# dalibor-display.net
KiCad netlist of a schematic drawn in Altium Designer
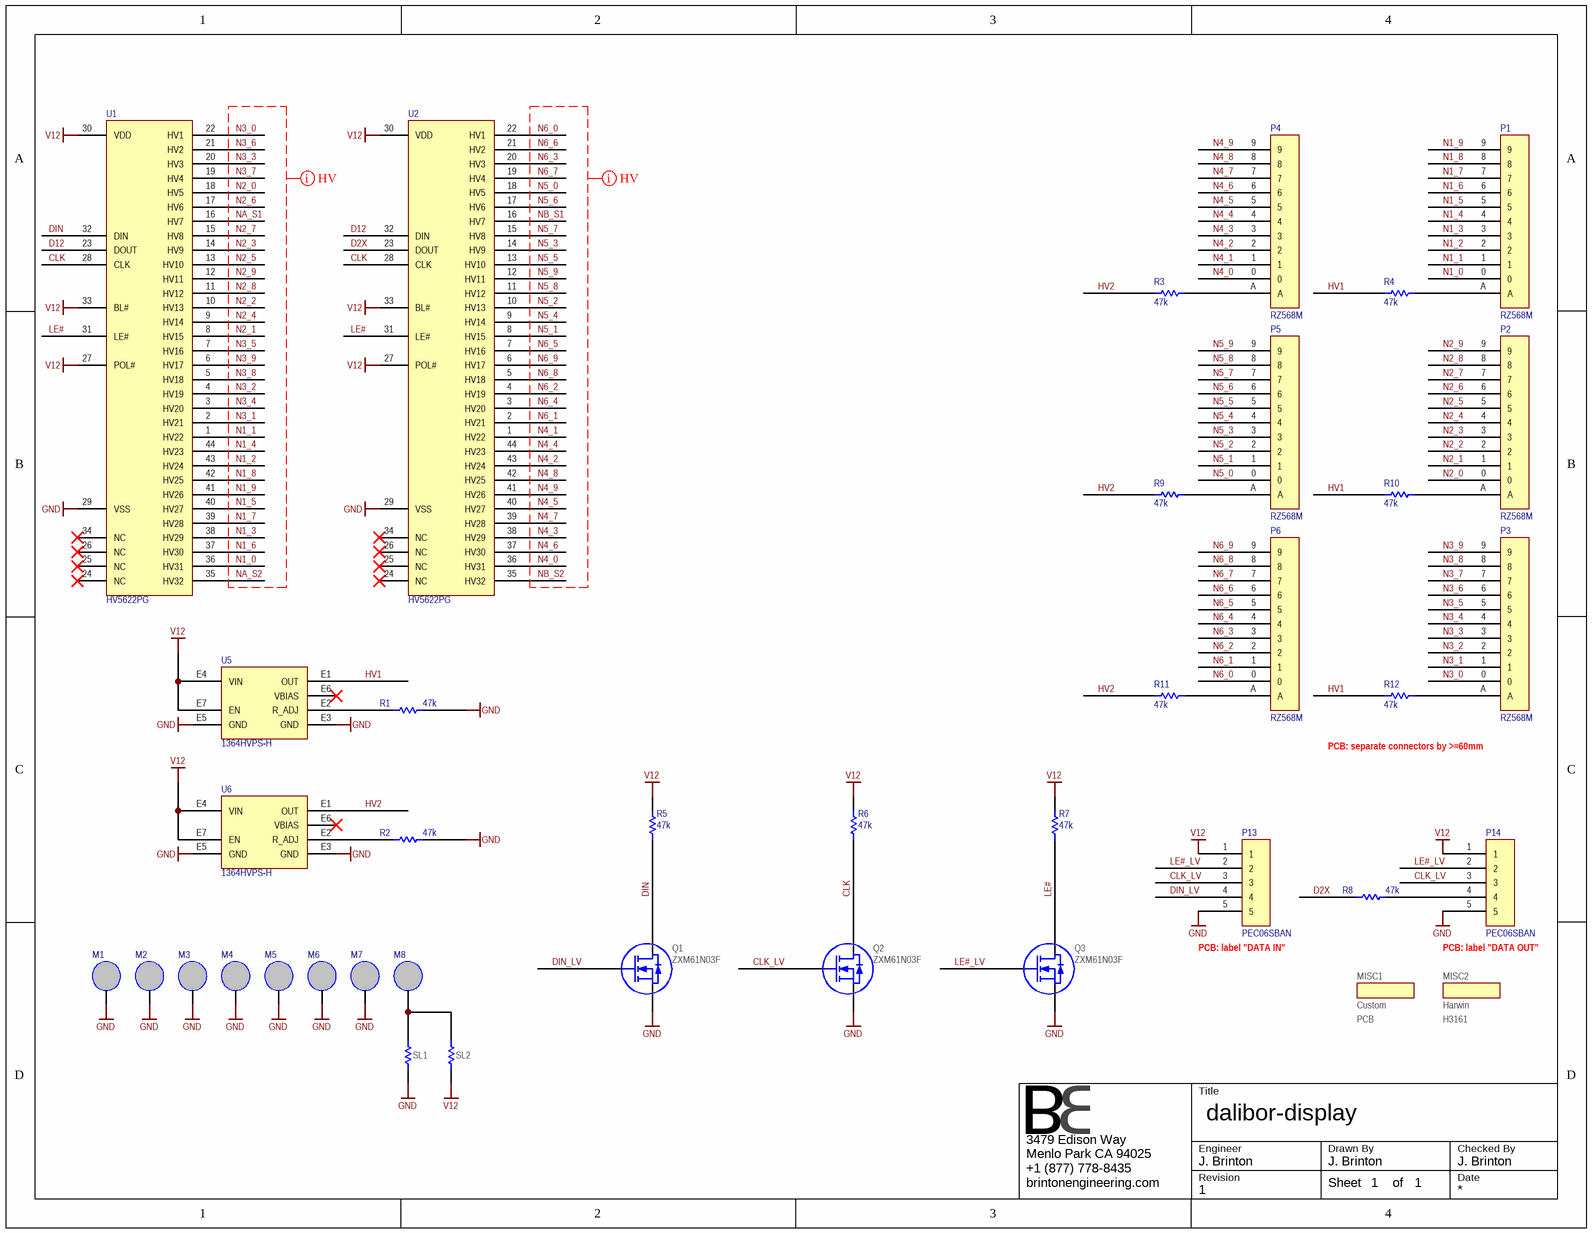
[diagram p0: dalibor-display.SchDoc]

(export (version "E")
  (design (tool "Eeschema 10.0.6"))
  (components
    (comp (ref "M1") (value "MOUNT") (footprint "MOUNT1-4_20") (libsource (lib "generic") (part "MOUNT")))
    (comp (ref "M2") (value "MOUNT") (footprint "MOUNT1-4_20") (libsource (lib "generic") (part "MOUNT")))
    (comp (ref "M3") (value "MOUNT") (footprint "MOUNT1-4_20") (libsource (lib "generic") (part "MOUNT")))
    (comp (ref "M4") (value "MOUNT") (footprint "MOUNT1-4_20") (libsource (lib "generic") (part "MOUNT")))
    (comp (ref "M5") (value "MOUNT") (footprint "MOUNT1-4_20") (libsource (lib "generic") (part "MOUNT")))
    (comp (ref "M6") (value "MOUNT") (footprint "MOUNT1-4_20") (libsource (lib "generic") (part "MOUNT")))
    (comp (ref "M7") (value "MOUNT") (footprint "MOUNT1-4_20") (libsource (lib "generic") (part "MOUNT")))
    (comp (ref "M8") (value "MOUNT") (footprint "MOUNT1-4_20") (libsource (lib "generic") (part "MOUNT")))
    (comp (ref "MISC1")
      (value "PCB")
      (fields (field (name "MANUFACTURER") "Custom"))
      (libsource (lib "harwin") (part "M50-1900005"))
    )
    (comp (ref "MISC2")
      (value "H3161")
      (description "Pin Receptacle")
      (fields (field (name "MANUFACTURER") "Harwin"))
      (libsource (lib "harwin") (part "M50-1900005"))
    )
    (comp (ref "P1")
      (value "RZ568M")
      (footprint "RZ568M")
      (description "Nixie Tube Socket")
      (fields (field (name "MANUFACTURER") "Glow Tube Research"))
      (libsource (lib "sigsub") (part "RZ568M"))
    )
    (comp (ref "P2")
      (value "RZ568M")
      (footprint "RZ568M")
      (description "Nixie Tube Socket")
      (fields (field (name "MANUFACTURER") "Glow Tube Research"))
      (libsource (lib "sigsub") (part "RZ568M"))
    )
    (comp (ref "P3")
      (value "RZ568M")
      (footprint "RZ568M")
      (description "Nixie Tube Socket")
      (fields (field (name "MANUFACTURER") "Glow Tube Research"))
      (libsource (lib "sigsub") (part "RZ568M"))
    )
    (comp (ref "P4")
      (value "RZ568M")
      (footprint "RZ568M")
      (description "Nixie Tube Socket")
      (fields (field (name "MANUFACTURER") "Glow Tube Research"))
      (libsource (lib "sigsub") (part "RZ568M"))
    )
    (comp (ref "P5")
      (value "RZ568M")
      (footprint "RZ568M")
      (description "Nixie Tube Socket")
      (fields (field (name "MANUFACTURER") "Glow Tube Research"))
      (libsource (lib "sigsub") (part "RZ568M"))
    )
    (comp (ref "P6")
      (value "RZ568M")
      (footprint "RZ568M")
      (description "Nixie Tube Socket")
      (fields (field (name "MANUFACTURER") "Glow Tube Research"))
      (libsource (lib "sigsub") (part "RZ568M"))
    )
    (comp (ref "P13")
      (value "PEC06SBAN")
      (footprint "HDR1X5")
      (description "Header, 5-Pin, Right Angle, 0.1\" pitch")
      (fields (field (name "MANUFACTURER") "Sullins"))
      (libsource (lib "sigsub") (part "PEC06SBAN"))
    )
    (comp (ref "P14")
      (value "PEC06SBAN")
      (footprint "HDR1X5")
      (description "Header, 5-Pin, Right Angle, 0.1\" pitch")
      (fields (field (name "MANUFACTURER") "Sullins"))
      (libsource (lib "sigsub") (part "PEC06SBAN"))
    )
    (comp (ref "Q1")
      (value "ZXM61N03F")
      (footprint "SOT23")
      (description "N-Channel Enhancement Mode MOSFET transistor")
      (fields (field (name "MANUFACTURER") "Zetex"))
      (libsource (lib "nxp") (part "BSH103"))
    )
    (comp (ref "Q2")
      (value "ZXM61N03F")
      (footprint "SOT23")
      (description "N-Channel Enhancement Mode MOSFET transistor")
      (fields (field (name "MANUFACTURER") "Zetex"))
      (libsource (lib "nxp") (part "BSH103"))
    )
    (comp (ref "Q3")
      (value "ZXM61N03F")
      (footprint "SOT23")
      (description "N-Channel Enhancement Mode MOSFET transistor")
      (fields (field (name "MANUFACTURER") "Zetex"))
      (libsource (lib "nxp") (part "BSH103"))
    )
    (comp (ref "R1")
      (value "47k")
      (footprint "0805")
      (description "Thick Film Resistor 47k +/-1% 0805")
      (fields (field (name "MANUFACTURER") "Panasonic") (field (name "Comment") "ERJ-6ENF4702V"))
      (libsource (lib "generic") (part "RES"))
    )
    (comp (ref "R2")
      (value "47k")
      (footprint "0805")
      (description "Thick Film Resistor 47k +/-1% 0805")
      (fields (field (name "MANUFACTURER") "Panasonic") (field (name "Comment") "ERJ-6ENF4702V"))
      (libsource (lib "generic") (part "RES"))
    )
    (comp (ref "R3")
      (value "47k")
      (footprint "0805")
      (description "Thick Film Resistor 47k +/-1% 0805")
      (fields (field (name "MANUFACTURER") "Panasonic") (field (name "Comment") "ERJ-6ENF4702V"))
      (libsource (lib "generic") (part "RES"))
    )
    (comp (ref "R4")
      (value "47k")
      (footprint "0805")
      (description "Thick Film Resistor 47k +/-1% 0805")
      (fields (field (name "MANUFACTURER") "Panasonic") (field (name "Comment") "ERJ-6ENF4702V"))
      (libsource (lib "generic") (part "RES"))
    )
    (comp (ref "R5")
      (value "47k")
      (footprint "0805")
      (description "Thick Film Resistor 47k +/-1% 0805")
      (fields (field (name "MANUFACTURER") "Panasonic") (field (name "Comment") "ERJ-6ENF4702V"))
      (libsource (lib "generic") (part "RES"))
    )
    (comp (ref "R6")
      (value "47k")
      (footprint "0805")
      (description "Thick Film Resistor 47k +/-1% 0805")
      (fields (field (name "MANUFACTURER") "Panasonic") (field (name "Comment") "ERJ-6ENF4702V"))
      (libsource (lib "generic") (part "RES"))
    )
    (comp (ref "R7")
      (value "47k")
      (footprint "0805")
      (description "Thick Film Resistor 47k +/-1% 0805")
      (fields (field (name "MANUFACTURER") "Panasonic") (field (name "Comment") "ERJ-6ENF4702V"))
      (libsource (lib "generic") (part "RES"))
    )
    (comp (ref "R8")
      (value "47k")
      (footprint "0805")
      (description "Thick Film Resistor 47k +/-1% 0805")
      (fields (field (name "MANUFACTURER") "Panasonic") (field (name "Comment") "ERJ-6ENF4702V"))
      (libsource (lib "generic") (part "RES"))
    )
    (comp (ref "R9")
      (value "47k")
      (footprint "0805")
      (description "Thick Film Resistor 47k +/-1% 0805")
      (fields (field (name "MANUFACTURER") "Panasonic") (field (name "Comment") "ERJ-6ENF4702V"))
      (libsource (lib "generic") (part "RES"))
    )
    (comp (ref "R10")
      (value "47k")
      (footprint "0805")
      (description "Thick Film Resistor 47k +/-1% 0805")
      (fields (field (name "MANUFACTURER") "Panasonic") (field (name "Comment") "ERJ-6ENF4702V"))
      (libsource (lib "generic") (part "RES"))
    )
    (comp (ref "R11")
      (value "47k")
      (footprint "0805")
      (description "Thick Film Resistor 47k +/-1% 0805")
      (fields (field (name "MANUFACTURER") "Panasonic") (field (name "Comment") "ERJ-6ENF4702V"))
      (libsource (lib "generic") (part "RES"))
    )
    (comp (ref "R12")
      (value "47k")
      (footprint "0805")
      (description "Thick Film Resistor 47k +/-1% 0805")
      (fields (field (name "MANUFACTURER") "Panasonic") (field (name "Comment") "ERJ-6ENF4702V"))
      (libsource (lib "generic") (part "RES"))
    )
    (comp (ref "SL1")
      (value "SOLDER_LINK")
      (footprint "SOLDERLINK0603X26N")
      (description "Solder Link")
      (libsource (lib "generic") (part "RES"))
    )
    (comp (ref "SL2")
      (value "SOLDER_LINK")
      (footprint "SOLDERLINK0603X26N")
      (description "Solder Link")
      (libsource (lib "generic") (part "RES"))
    )
    (comp (ref "U1")
      (value "HV5622PG")
      (footprint "QFP44P80_1390X1390X235L88X37N")
      (description "32-Channel Serial to Parallel Converter")
      (fields (field (name "MANUFACTURER") "Microchip"))
      (libsource (lib "sigsub") (part "HV5622PG"))
    )
    (comp (ref "U2")
      (value "HV5622PG")
      (footprint "QFP44P80_1390X1390X235L88X37N")
      (description "32-Channel Serial to Parallel Converter")
      (fields (field (name "MANUFACTURER") "Microchip"))
      (libsource (lib "sigsub") (part "HV5622PG"))
    )
    (comp (ref "U5")
      (value "1364HVPS-H")
      (footprint "1364HVPS-H")
      (description "High Voltage Power Supply")
      (fields (field (name "MANUFACTURER") "Taylor Electronics"))
      (libsource (lib "sigsub") (part "1364HVPS-H"))
    )
    (comp (ref "U6")
      (value "1364HVPS-H")
      (footprint "1364HVPS-H")
      (description "High Voltage Power Supply")
      (fields (field (name "MANUFACTURER") "Taylor Electronics"))
      (libsource (lib "sigsub") (part "1364HVPS-H"))
    )
  )
  (nets
    (net (code "1") (name "/CLK") (class "Default")
      (node (ref "Q2") (pin "3") (pinfunction "D_3") (pintype "passive"))
      (node (ref "R6") (pin "1") (pinfunction "1_1") (pintype "passive"))
      (node (ref "U1") (pin "28") (pinfunction "CLK_28") (pintype "passive"))
      (node (ref "U2") (pin "28") (pinfunction "CLK_28") (pintype "passive"))
    )
    (net (code "2") (name "/CLK_LV") (class "Default")
      (node (ref "P13") (pin "3") (pinfunction "3_3") (pintype "passive"))
      (node (ref "P14") (pin "3") (pinfunction "3_3") (pintype "passive"))
      (node (ref "Q2") (pin "1") (pinfunction "G_1") (pintype "passive"))
    )
    (net (code "3") (name "/D2X") (class "Default")
      (node (ref "R8") (pin "1") (pinfunction "1_1") (pintype "passive"))
      (node (ref "U2") (pin "23") (pinfunction "DOUT_23") (pintype "passive"))
    )
    (net (code "4") (name "/D12") (class "Default")
      (node (ref "U1") (pin "23") (pinfunction "DOUT_23") (pintype "passive"))
      (node (ref "U2") (pin "32") (pinfunction "DIN_32") (pintype "passive"))
    )
    (net (code "5") (name "/DIN") (class "Default")
      (node (ref "Q1") (pin "3") (pinfunction "D_3") (pintype "passive"))
      (node (ref "R5") (pin "1") (pinfunction "1_1") (pintype "passive"))
      (node (ref "U1") (pin "32") (pinfunction "DIN_32") (pintype "passive"))
    )
    (net (code "6") (name "/DIN_LV") (class "Default")
      (node (ref "P13") (pin "4") (pinfunction "4_4") (pintype "passive"))
      (node (ref "Q1") (pin "1") (pinfunction "G_1") (pintype "passive"))
    )
    (net (code "7") (name "/HV1") (class "Default")
      (node (ref "R10") (pin "2") (pinfunction "2_2") (pintype "passive"))
      (node (ref "R12") (pin "2") (pinfunction "2_2") (pintype "passive"))
      (node (ref "R4") (pin "2") (pinfunction "2_2") (pintype "passive"))
      (node (ref "U5") (pin "E1") (pinfunction "OUT_E1") (pintype "passive"))
    )
    (net (code "8") (name "/HV2") (class "Default")
      (node (ref "R11") (pin "2") (pinfunction "2_2") (pintype "passive"))
      (node (ref "R3") (pin "2") (pinfunction "2_2") (pintype "passive"))
      (node (ref "R9") (pin "2") (pinfunction "2_2") (pintype "passive"))
      (node (ref "U6") (pin "E1") (pinfunction "OUT_E1") (pintype "passive"))
    )
    (net (code "9") (name "/LE#") (class "Default")
      (node (ref "Q3") (pin "3") (pinfunction "D_3") (pintype "passive"))
      (node (ref "R7") (pin "1") (pinfunction "1_1") (pintype "passive"))
      (node (ref "U1") (pin "31") (pinfunction "LE#_31") (pintype "passive"))
      (node (ref "U2") (pin "31") (pinfunction "LE#_31") (pintype "passive"))
    )
    (net (code "10") (name "/LE#_LV") (class "Default")
      (node (ref "P13") (pin "2") (pinfunction "2_2") (pintype "passive"))
      (node (ref "P14") (pin "2") (pinfunction "2_2") (pintype "passive"))
      (node (ref "Q3") (pin "1") (pinfunction "G_1") (pintype "passive"))
    )
    (net (code "11") (name "/N1_0") (class "Default")
      (node (ref "P1") (pin "0") (pinfunction "0_0") (pintype "passive"))
      (node (ref "U1") (pin "36") (pinfunction "HV31_36") (pintype "passive"))
    )
    (net (code "12") (name "/N1_1") (class "Default")
      (node (ref "P1") (pin "1") (pinfunction "1_1") (pintype "passive"))
      (node (ref "U1") (pin "1") (pinfunction "HV22_1") (pintype "passive"))
    )
    (net (code "13") (name "/N1_2") (class "Default")
      (node (ref "P1") (pin "2") (pinfunction "2_2") (pintype "passive"))
      (node (ref "U1") (pin "43") (pinfunction "HV24_43") (pintype "passive"))
    )
    (net (code "14") (name "/N1_3") (class "Default")
      (node (ref "P1") (pin "3") (pinfunction "3_3") (pintype "passive"))
      (node (ref "U1") (pin "38") (pinfunction "HV29_38") (pintype "passive"))
    )
    (net (code "15") (name "/N1_4") (class "Default")
      (node (ref "P1") (pin "4") (pinfunction "4_4") (pintype "passive"))
      (node (ref "U1") (pin "44") (pinfunction "HV23_44") (pintype "passive"))
    )
    (net (code "16") (name "/N1_5") (class "Default")
      (node (ref "P1") (pin "5") (pinfunction "5_5") (pintype "passive"))
      (node (ref "U1") (pin "40") (pinfunction "HV27_40") (pintype "passive"))
    )
    (net (code "17") (name "/N1_6") (class "Default")
      (node (ref "P1") (pin "6") (pinfunction "6_6") (pintype "passive"))
      (node (ref "U1") (pin "37") (pinfunction "HV30_37") (pintype "passive"))
    )
    (net (code "18") (name "/N1_7") (class "Default")
      (node (ref "P1") (pin "7") (pinfunction "7_7") (pintype "passive"))
      (node (ref "U1") (pin "39") (pinfunction "HV28_39") (pintype "passive"))
    )
    (net (code "19") (name "/N1_8") (class "Default")
      (node (ref "P1") (pin "8") (pinfunction "8_8") (pintype "passive"))
      (node (ref "U1") (pin "42") (pinfunction "HV25_42") (pintype "passive"))
    )
    (net (code "20") (name "/N1_9") (class "Default")
      (node (ref "P1") (pin "9") (pinfunction "9_9") (pintype "passive"))
      (node (ref "U1") (pin "41") (pinfunction "HV26_41") (pintype "passive"))
    )
    (net (code "21") (name "/N2_0") (class "Default")
      (node (ref "P2") (pin "0") (pinfunction "0_0") (pintype "passive"))
      (node (ref "U1") (pin "18") (pinfunction "HV5_18") (pintype "passive"))
    )
    (net (code "22") (name "/N2_1") (class "Default")
      (node (ref "P2") (pin "1") (pinfunction "1_1") (pintype "passive"))
      (node (ref "U1") (pin "8") (pinfunction "HV15_8") (pintype "passive"))
    )
    (net (code "23") (name "/N2_2") (class "Default")
      (node (ref "P2") (pin "2") (pinfunction "2_2") (pintype "passive"))
      (node (ref "U1") (pin "10") (pinfunction "HV13_10") (pintype "passive"))
    )
    (net (code "24") (name "/N2_3") (class "Default")
      (node (ref "P2") (pin "3") (pinfunction "3_3") (pintype "passive"))
      (node (ref "U1") (pin "14") (pinfunction "HV9_14") (pintype "passive"))
    )
    (net (code "25") (name "/N2_4") (class "Default")
      (node (ref "P2") (pin "4") (pinfunction "4_4") (pintype "passive"))
      (node (ref "U1") (pin "9") (pinfunction "HV14_9") (pintype "passive"))
    )
    (net (code "26") (name "/N2_5") (class "Default")
      (node (ref "P2") (pin "5") (pinfunction "5_5") (pintype "passive"))
      (node (ref "U1") (pin "13") (pinfunction "HV10_13") (pintype "passive"))
    )
    (net (code "27") (name "/N2_6") (class "Default")
      (node (ref "P2") (pin "6") (pinfunction "6_6") (pintype "passive"))
      (node (ref "U1") (pin "17") (pinfunction "HV6_17") (pintype "passive"))
    )
    (net (code "28") (name "/N2_7") (class "Default")
      (node (ref "P2") (pin "7") (pinfunction "7_7") (pintype "passive"))
      (node (ref "U1") (pin "15") (pinfunction "HV8_15") (pintype "passive"))
    )
    (net (code "29") (name "/N2_8") (class "Default")
      (node (ref "P2") (pin "8") (pinfunction "8_8") (pintype "passive"))
      (node (ref "U1") (pin "11") (pinfunction "HV12_11") (pintype "passive"))
    )
    (net (code "30") (name "/N2_9") (class "Default")
      (node (ref "P2") (pin "9") (pinfunction "9_9") (pintype "passive"))
      (node (ref "U1") (pin "12") (pinfunction "HV11_12") (pintype "passive"))
    )
    (net (code "31") (name "/N3_0") (class "Default")
      (node (ref "P3") (pin "0") (pinfunction "0_0") (pintype "passive"))
      (node (ref "U1") (pin "22") (pinfunction "HV1_22") (pintype "passive"))
    )
    (net (code "32") (name "/N3_1") (class "Default")
      (node (ref "P3") (pin "1") (pinfunction "1_1") (pintype "passive"))
      (node (ref "U1") (pin "2") (pinfunction "HV21_2") (pintype "passive"))
    )
    (net (code "33") (name "/N3_2") (class "Default")
      (node (ref "P3") (pin "2") (pinfunction "2_2") (pintype "passive"))
      (node (ref "U1") (pin "4") (pinfunction "HV19_4") (pintype "passive"))
    )
    (net (code "34") (name "/N3_3") (class "Default")
      (node (ref "P3") (pin "3") (pinfunction "3_3") (pintype "passive"))
      (node (ref "U1") (pin "20") (pinfunction "HV3_20") (pintype "passive"))
    )
    (net (code "35") (name "/N3_4") (class "Default")
      (node (ref "P3") (pin "4") (pinfunction "4_4") (pintype "passive"))
      (node (ref "U1") (pin "3") (pinfunction "HV20_3") (pintype "passive"))
    )
    (net (code "36") (name "/N3_5") (class "Default")
      (node (ref "P3") (pin "5") (pinfunction "5_5") (pintype "passive"))
      (node (ref "U1") (pin "7") (pinfunction "HV16_7") (pintype "passive"))
    )
    (net (code "37") (name "/N3_6") (class "Default")
      (node (ref "P3") (pin "6") (pinfunction "6_6") (pintype "passive"))
      (node (ref "U1") (pin "21") (pinfunction "HV2_21") (pintype "passive"))
    )
    (net (code "38") (name "/N3_7") (class "Default")
      (node (ref "P3") (pin "7") (pinfunction "7_7") (pintype "passive"))
      (node (ref "U1") (pin "19") (pinfunction "HV4_19") (pintype "passive"))
    )
    (net (code "39") (name "/N3_8") (class "Default")
      (node (ref "P3") (pin "8") (pinfunction "8_8") (pintype "passive"))
      (node (ref "U1") (pin "5") (pinfunction "HV18_5") (pintype "passive"))
    )
    (net (code "40") (name "/N3_9") (class "Default")
      (node (ref "P3") (pin "9") (pinfunction "9_9") (pintype "passive"))
      (node (ref "U1") (pin "6") (pinfunction "HV17_6") (pintype "passive"))
    )
    (net (code "41") (name "/N4_0") (class "Default")
      (node (ref "P4") (pin "0") (pinfunction "0_0") (pintype "passive"))
      (node (ref "U2") (pin "36") (pinfunction "HV31_36") (pintype "passive"))
    )
    (net (code "42") (name "/N4_1") (class "Default")
      (node (ref "P4") (pin "1") (pinfunction "1_1") (pintype "passive"))
      (node (ref "U2") (pin "1") (pinfunction "HV22_1") (pintype "passive"))
    )
    (net (code "43") (name "/N4_2") (class "Default")
      (node (ref "P4") (pin "2") (pinfunction "2_2") (pintype "passive"))
      (node (ref "U2") (pin "43") (pinfunction "HV24_43") (pintype "passive"))
    )
    (net (code "44") (name "/N4_3") (class "Default")
      (node (ref "P4") (pin "3") (pinfunction "3_3") (pintype "passive"))
      (node (ref "U2") (pin "38") (pinfunction "HV29_38") (pintype "passive"))
    )
    (net (code "45") (name "/N4_4") (class "Default")
      (node (ref "P4") (pin "4") (pinfunction "4_4") (pintype "passive"))
      (node (ref "U2") (pin "44") (pinfunction "HV23_44") (pintype "passive"))
    )
    (net (code "46") (name "/N4_5") (class "Default")
      (node (ref "P4") (pin "5") (pinfunction "5_5") (pintype "passive"))
      (node (ref "U2") (pin "40") (pinfunction "HV27_40") (pintype "passive"))
    )
    (net (code "47") (name "/N4_6") (class "Default")
      (node (ref "P4") (pin "6") (pinfunction "6_6") (pintype "passive"))
      (node (ref "U2") (pin "37") (pinfunction "HV30_37") (pintype "passive"))
    )
    (net (code "48") (name "/N4_7") (class "Default")
      (node (ref "P4") (pin "7") (pinfunction "7_7") (pintype "passive"))
      (node (ref "U2") (pin "39") (pinfunction "HV28_39") (pintype "passive"))
    )
    (net (code "49") (name "/N4_8") (class "Default")
      (node (ref "P4") (pin "8") (pinfunction "8_8") (pintype "passive"))
      (node (ref "U2") (pin "42") (pinfunction "HV25_42") (pintype "passive"))
    )
    (net (code "50") (name "/N4_9") (class "Default")
      (node (ref "P4") (pin "9") (pinfunction "9_9") (pintype "passive"))
      (node (ref "U2") (pin "41") (pinfunction "HV26_41") (pintype "passive"))
    )
    (net (code "51") (name "/N5_0") (class "Default")
      (node (ref "P5") (pin "0") (pinfunction "0_0") (pintype "passive"))
      (node (ref "U2") (pin "18") (pinfunction "HV5_18") (pintype "passive"))
    )
    (net (code "52") (name "/N5_1") (class "Default")
      (node (ref "P5") (pin "1") (pinfunction "1_1") (pintype "passive"))
      (node (ref "U2") (pin "8") (pinfunction "HV15_8") (pintype "passive"))
    )
    (net (code "53") (name "/N5_2") (class "Default")
      (node (ref "P5") (pin "2") (pinfunction "2_2") (pintype "passive"))
      (node (ref "U2") (pin "10") (pinfunction "HV13_10") (pintype "passive"))
    )
    (net (code "54") (name "/N5_3") (class "Default")
      (node (ref "P5") (pin "3") (pinfunction "3_3") (pintype "passive"))
      (node (ref "U2") (pin "14") (pinfunction "HV9_14") (pintype "passive"))
    )
    (net (code "55") (name "/N5_4") (class "Default")
      (node (ref "P5") (pin "4") (pinfunction "4_4") (pintype "passive"))
      (node (ref "U2") (pin "9") (pinfunction "HV14_9") (pintype "passive"))
    )
    (net (code "56") (name "/N5_5") (class "Default")
      (node (ref "P5") (pin "5") (pinfunction "5_5") (pintype "passive"))
      (node (ref "U2") (pin "13") (pinfunction "HV10_13") (pintype "passive"))
    )
    (net (code "57") (name "/N5_6") (class "Default")
      (node (ref "P5") (pin "6") (pinfunction "6_6") (pintype "passive"))
      (node (ref "U2") (pin "17") (pinfunction "HV6_17") (pintype "passive"))
    )
    (net (code "58") (name "/N5_7") (class "Default")
      (node (ref "P5") (pin "7") (pinfunction "7_7") (pintype "passive"))
      (node (ref "U2") (pin "15") (pinfunction "HV8_15") (pintype "passive"))
    )
    (net (code "59") (name "/N5_8") (class "Default")
      (node (ref "P5") (pin "8") (pinfunction "8_8") (pintype "passive"))
      (node (ref "U2") (pin "11") (pinfunction "HV12_11") (pintype "passive"))
    )
    (net (code "60") (name "/N5_9") (class "Default")
      (node (ref "P5") (pin "9") (pinfunction "9_9") (pintype "passive"))
      (node (ref "U2") (pin "12") (pinfunction "HV11_12") (pintype "passive"))
    )
    (net (code "61") (name "/N6_0") (class "Default")
      (node (ref "P6") (pin "0") (pinfunction "0_0") (pintype "passive"))
      (node (ref "U2") (pin "22") (pinfunction "HV1_22") (pintype "passive"))
    )
    (net (code "62") (name "/N6_1") (class "Default")
      (node (ref "P6") (pin "1") (pinfunction "1_1") (pintype "passive"))
      (node (ref "U2") (pin "2") (pinfunction "HV21_2") (pintype "passive"))
    )
    (net (code "63") (name "/N6_2") (class "Default")
      (node (ref "P6") (pin "2") (pinfunction "2_2") (pintype "passive"))
      (node (ref "U2") (pin "4") (pinfunction "HV19_4") (pintype "passive"))
    )
    (net (code "64") (name "/N6_3") (class "Default")
      (node (ref "P6") (pin "3") (pinfunction "3_3") (pintype "passive"))
      (node (ref "U2") (pin "20") (pinfunction "HV3_20") (pintype "passive"))
    )
    (net (code "65") (name "/N6_4") (class "Default")
      (node (ref "P6") (pin "4") (pinfunction "4_4") (pintype "passive"))
      (node (ref "U2") (pin "3") (pinfunction "HV20_3") (pintype "passive"))
    )
    (net (code "66") (name "/N6_5") (class "Default")
      (node (ref "P6") (pin "5") (pinfunction "5_5") (pintype "passive"))
      (node (ref "U2") (pin "7") (pinfunction "HV16_7") (pintype "passive"))
    )
    (net (code "67") (name "/N6_6") (class "Default")
      (node (ref "P6") (pin "6") (pinfunction "6_6") (pintype "passive"))
      (node (ref "U2") (pin "21") (pinfunction "HV2_21") (pintype "passive"))
    )
    (net (code "68") (name "/N6_7") (class "Default")
      (node (ref "P6") (pin "7") (pinfunction "7_7") (pintype "passive"))
      (node (ref "U2") (pin "19") (pinfunction "HV4_19") (pintype "passive"))
    )
    (net (code "69") (name "/N6_8") (class "Default")
      (node (ref "P6") (pin "8") (pinfunction "8_8") (pintype "passive"))
      (node (ref "U2") (pin "5") (pinfunction "HV18_5") (pintype "passive"))
    )
    (net (code "70") (name "/N6_9") (class "Default")
      (node (ref "P6") (pin "9") (pinfunction "9_9") (pintype "passive"))
      (node (ref "U2") (pin "6") (pinfunction "HV17_6") (pintype "passive"))
    )
    (net (code "71") (name "/NA_S1") (class "Default")
      (node (ref "U1") (pin "16") (pinfunction "HV7_16") (pintype "passive"))
    )
    (net (code "72") (name "/NA_S2") (class "Default")
      (node (ref "U1") (pin "35") (pinfunction "HV32_35") (pintype "passive"))
    )
    (net (code "73") (name "/NB_S1") (class "Default")
      (node (ref "U2") (pin "16") (pinfunction "HV7_16") (pintype "passive"))
    )
    (net (code "74") (name "/NB_S2") (class "Default")
      (node (ref "U2") (pin "35") (pinfunction "HV32_35") (pintype "passive"))
    )
    (net (code "75") (name "GND") (class "Default")
      (node (ref "M1") (pin "1") (pinfunction "MNT_1") (pintype "passive"))
      (node (ref "M2") (pin "1") (pinfunction "MNT_1") (pintype "passive"))
      (node (ref "M3") (pin "1") (pinfunction "MNT_1") (pintype "passive"))
      (node (ref "M4") (pin "1") (pinfunction "MNT_1") (pintype "passive"))
      (node (ref "M5") (pin "1") (pinfunction "MNT_1") (pintype "passive"))
      (node (ref "M6") (pin "1") (pinfunction "MNT_1") (pintype "passive"))
      (node (ref "M7") (pin "1") (pinfunction "MNT_1") (pintype "passive"))
      (node (ref "P13") (pin "5") (pinfunction "5_5") (pintype "passive"))
      (node (ref "P14") (pin "5") (pinfunction "5_5") (pintype "passive"))
      (node (ref "Q1") (pin "2") (pinfunction "S_2") (pintype "passive"))
      (node (ref "Q2") (pin "2") (pinfunction "S_2") (pintype "passive"))
      (node (ref "Q3") (pin "2") (pinfunction "S_2") (pintype "passive"))
      (node (ref "R1") (pin "2") (pinfunction "2_2") (pintype "passive"))
      (node (ref "R2") (pin "2") (pinfunction "2_2") (pintype "passive"))
      (node (ref "SL1") (pin "2") (pinfunction "2_2") (pintype "passive"))
      (node (ref "U1") (pin "29") (pinfunction "VSS_29") (pintype "passive"))
      (node (ref "U2") (pin "29") (pinfunction "VSS_29") (pintype "passive"))
      (node (ref "U5") (pin "E3") (pinfunction "GND_E3") (pintype "passive"))
      (node (ref "U5") (pin "E5") (pinfunction "GND_E5") (pintype "passive"))
      (node (ref "U6") (pin "E3") (pinfunction "GND_E3") (pintype "passive"))
      (node (ref "U6") (pin "E5") (pinfunction "GND_E5") (pintype "passive"))
    )
    (net (code "76") (name "Net-(M8-MNT)") (class "Default")
      (node (ref "M8") (pin "1") (pinfunction "MNT_1") (pintype "passive"))
      (node (ref "SL1") (pin "1") (pinfunction "1_1") (pintype "passive"))
      (node (ref "SL2") (pin "1") (pinfunction "1_1") (pintype "passive"))
    )
    (net (code "77") (name "Net-(P1-PadA)") (class "Default")
      (node (ref "P1") (pin "A") (pinfunction "A_A") (pintype "passive"))
      (node (ref "R4") (pin "1") (pinfunction "1_1") (pintype "passive"))
    )
    (net (code "78") (name "Net-(P2-PadA)") (class "Default")
      (node (ref "P2") (pin "A") (pinfunction "A_A") (pintype "passive"))
      (node (ref "R10") (pin "1") (pinfunction "1_1") (pintype "passive"))
    )
    (net (code "79") (name "Net-(P3-PadA)") (class "Default")
      (node (ref "P3") (pin "A") (pinfunction "A_A") (pintype "passive"))
      (node (ref "R12") (pin "1") (pinfunction "1_1") (pintype "passive"))
    )
    (net (code "80") (name "Net-(P4-PadA)") (class "Default")
      (node (ref "P4") (pin "A") (pinfunction "A_A") (pintype "passive"))
      (node (ref "R3") (pin "1") (pinfunction "1_1") (pintype "passive"))
    )
    (net (code "81") (name "Net-(P5-PadA)") (class "Default")
      (node (ref "P5") (pin "A") (pinfunction "A_A") (pintype "passive"))
      (node (ref "R9") (pin "1") (pinfunction "1_1") (pintype "passive"))
    )
    (net (code "82") (name "Net-(P6-PadA)") (class "Default")
      (node (ref "P6") (pin "A") (pinfunction "A_A") (pintype "passive"))
      (node (ref "R11") (pin "1") (pinfunction "1_1") (pintype "passive"))
    )
    (net (code "83") (name "Net-(P14-Pad4)") (class "Default")
      (node (ref "P14") (pin "4") (pinfunction "4_4") (pintype "passive"))
      (node (ref "R8") (pin "2") (pinfunction "2_2") (pintype "passive"))
    )
    (net (code "84") (name "Net-(U5-R_ADJ)") (class "Default")
      (node (ref "R1") (pin "1") (pinfunction "1_1") (pintype "passive"))
      (node (ref "U5") (pin "E2") (pinfunction "R_ADJ_E2") (pintype "passive"))
    )
    (net (code "85") (name "Net-(U6-R_ADJ)") (class "Default")
      (node (ref "R2") (pin "1") (pinfunction "1_1") (pintype "passive"))
      (node (ref "U6") (pin "E2") (pinfunction "R_ADJ_E2") (pintype "passive"))
    )
    (net (code "86") (name "V12") (class "Default")
      (node (ref "P13") (pin "1") (pinfunction "1_1") (pintype "passive"))
      (node (ref "P14") (pin "1") (pinfunction "1_1") (pintype "passive"))
      (node (ref "R5") (pin "2") (pinfunction "2_2") (pintype "passive"))
      (node (ref "R6") (pin "2") (pinfunction "2_2") (pintype "passive"))
      (node (ref "R7") (pin "2") (pinfunction "2_2") (pintype "passive"))
      (node (ref "SL2") (pin "2") (pinfunction "2_2") (pintype "passive"))
      (node (ref "U1") (pin "27") (pinfunction "POL#_27") (pintype "passive"))
      (node (ref "U1") (pin "30") (pinfunction "VDD_30") (pintype "passive"))
      (node (ref "U1") (pin "33") (pinfunction "BL#_33") (pintype "passive"))
      (node (ref "U2") (pin "27") (pinfunction "POL#_27") (pintype "passive"))
      (node (ref "U2") (pin "30") (pinfunction "VDD_30") (pintype "passive"))
      (node (ref "U2") (pin "33") (pinfunction "BL#_33") (pintype "passive"))
      (node (ref "U5") (pin "E4") (pinfunction "VIN_E4") (pintype "passive"))
      (node (ref "U5") (pin "E7") (pinfunction "EN_E7") (pintype "passive"))
      (node (ref "U6") (pin "E4") (pinfunction "VIN_E4") (pintype "passive"))
      (node (ref "U6") (pin "E7") (pinfunction "EN_E7") (pintype "passive"))
    )
    (net (code "87") (name "unconnected-(U1-NC-Pad24)") (class "Default")
      (node (ref "U1") (pin "24") (pinfunction "NC_24") (pintype "passive+no_connect"))
    )
    (net (code "88") (name "unconnected-(U1-NC-Pad25)") (class "Default")
      (node (ref "U1") (pin "25") (pinfunction "NC_25") (pintype "passive+no_connect"))
    )
    (net (code "89") (name "unconnected-(U1-NC-Pad26)") (class "Default")
      (node (ref "U1") (pin "26") (pinfunction "NC_26") (pintype "passive+no_connect"))
    )
    (net (code "90") (name "unconnected-(U1-NC-Pad34)") (class "Default")
      (node (ref "U1") (pin "34") (pinfunction "NC_34") (pintype "passive+no_connect"))
    )
    (net (code "91") (name "unconnected-(U2-NC-Pad24)") (class "Default")
      (node (ref "U2") (pin "24") (pinfunction "NC_24") (pintype "passive+no_connect"))
    )
    (net (code "92") (name "unconnected-(U2-NC-Pad25)") (class "Default")
      (node (ref "U2") (pin "25") (pinfunction "NC_25") (pintype "passive+no_connect"))
    )
    (net (code "93") (name "unconnected-(U2-NC-Pad26)") (class "Default")
      (node (ref "U2") (pin "26") (pinfunction "NC_26") (pintype "passive+no_connect"))
    )
    (net (code "94") (name "unconnected-(U2-NC-Pad34)") (class "Default")
      (node (ref "U2") (pin "34") (pinfunction "NC_34") (pintype "passive+no_connect"))
    )
    (net (code "95") (name "unconnected-(U5-VBIAS-PadE6)") (class "Default")
      (node (ref "U5") (pin "E6") (pinfunction "VBIAS_E6") (pintype "passive+no_connect"))
    )
    (net (code "96") (name "unconnected-(U6-VBIAS-PadE6)") (class "Default")
      (node (ref "U6") (pin "E6") (pinfunction "VBIAS_E6") (pintype "passive+no_connect"))
    )
  )
)
